# USB_0.net
KiCad netlist of a schematic drawn in Altium Designer
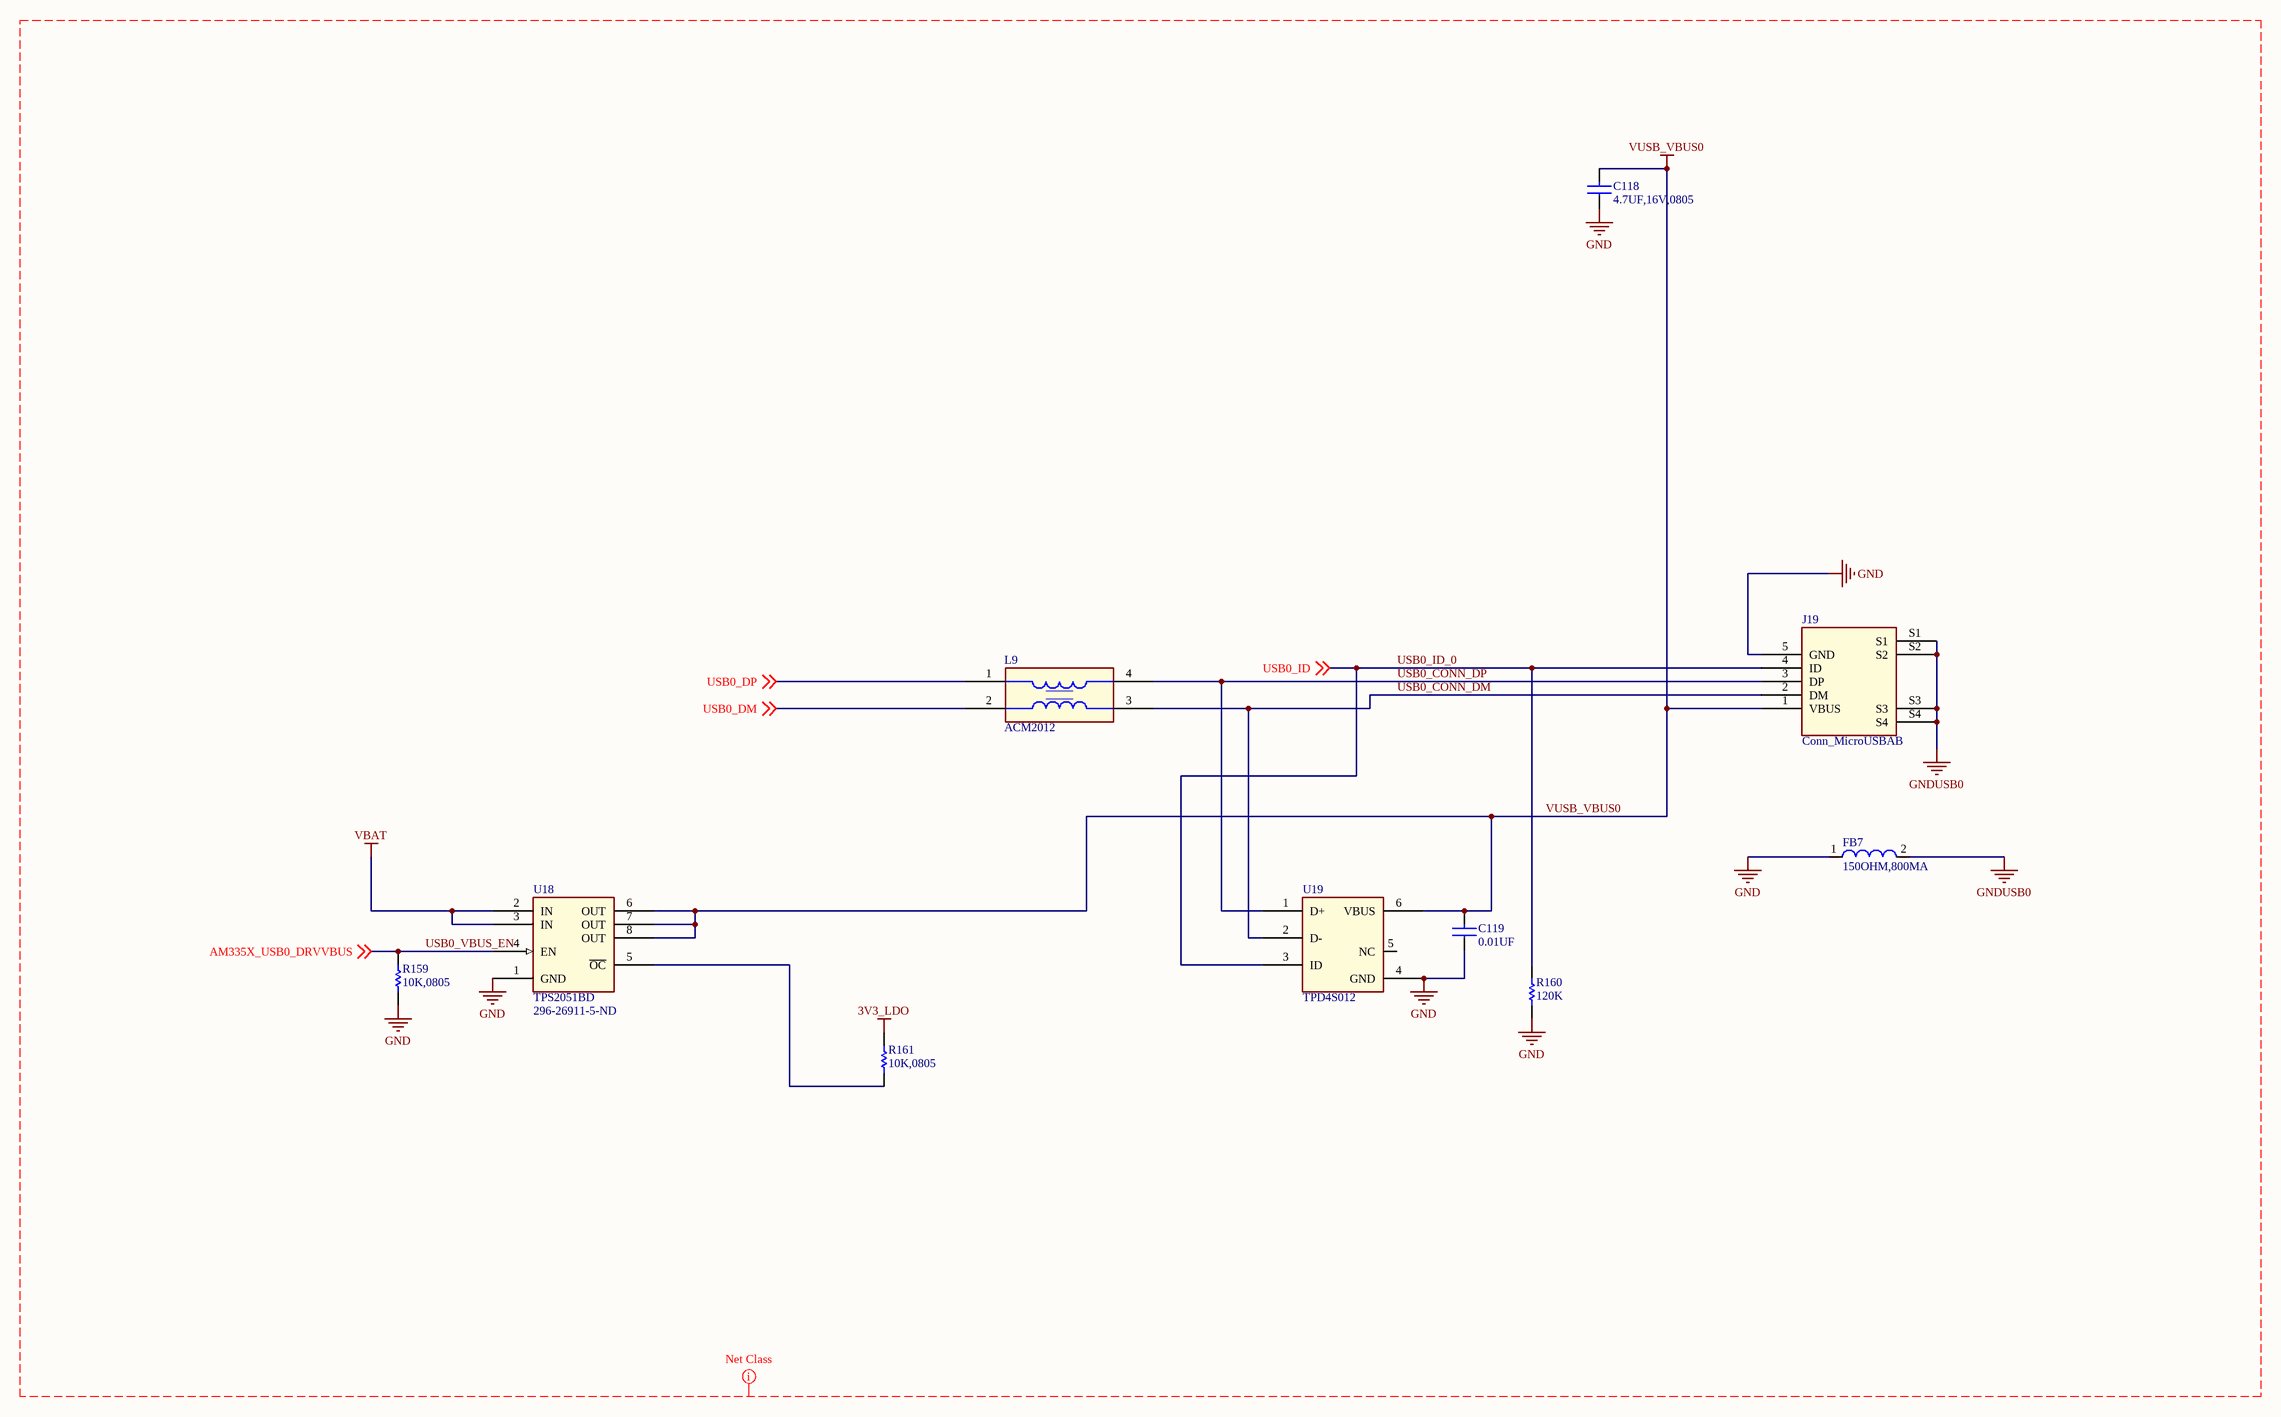
[diagram p0: USB_0.SchDoc]

(export (version "E")
  (design (tool "Eeschema 10.0.6"))
  (components
    (comp (ref "C118")
      (value "4.7UF,16V,0805")
      (footprint "0805")
      (description "AVX - 0805YC475KAT2A - CAP, MLCC, X7R, 4.7UF, 16V, 0805")
      (fields (field (name "MANUFACTURER") "AVX") (field (name "MANUFACTURER PART NUMBER") "0805YC475KAT2A"))
      (libsource (lib "LINUX") (part "4.7UF,16V,0805"))
    )
    (comp (ref "C119")
      (value "0.01UF")
      (footprint "0805")
      (description "MULTICOMP - MCSH21B103K100CT - CAP, MLCC, X7R, 10NF, 10V, 0805")
      (fields
        (field (name "MANUFACTURER") "MULTICOMP")
        (field (name "MANUFACTURER PART NUMBER") "MCSH21B103K100CT")
      )
      (libsource (lib "LINUX") (part "0.01UF"))
    )
    (comp (ref "FB7")
      (value "150OHM,800MA")
      (footprint "0805")
      (description "FERRITE 800MA 150 OHM 0805 SMD")
      (fields
        (field (name "MANUFACTURER") "Laird-Signal Integrity Products")
        (field (name "MANUFACTURER PART NUMBER") "LI0805H151R-10")
      )
      (libsource (lib "LINUX") (part "150OHM,800MA"))
    )
    (comp (ref "J19")
      (value "Conn_MicroUSBAB")
      (footprint "USB MINI TYPE B")
      (description "Connector Micro USB AB RA")
      (fields (field (name "TIINTPARTNUMBER") "2C0088") (field (name "MFR") "Hirose"))
      (libsource (lib "LINUX") (part "Conn_MicroUSBAB"))
    )
    (comp (ref "L9")
      (value "ACM2012")
      (footprint "ACM2012H")
      (description "Common Mode Filter for USB/HDMI")
      (fields (field (name "MFR") "TDK") (field (name "TIINTPARTNUMBER") "1M0003"))
      (libsource (lib "LINUX") (part "ACM2012"))
    )
    (comp (ref "R159")
      (value "10K,0805")
      (footprint "0805")
      (description "BOURNS - CR0805-FX-1002GLF - RESISTOR, 10K, 0.125W, 1%")
      (fields
        (field (name "MANUFACTURER") "BOURNS")
        (field (name "MANUFACTURER PART NUMBER") "CR0805-FX-1002GLF")
      )
      (libsource (lib "LINUX") (part "10K,0805"))
    )
    (comp (ref "R160")
      (value "120K")
      (footprint "0805")
      (description "TE CONNECTIVITY - CRGH0805F120K - RESISTOR, POWER, 120K, 0.33W, 1%, 0805")
      (fields
        (field (name "MANUFACTURER") "TE CONNECTIVITY")
        (field (name "MANUFACTURER PART NUMBER") "CRGH0805F120K")
      )
      (libsource (lib "LINUX") (part "120K"))
    )
    (comp (ref "R161")
      (value "10K,0805")
      (footprint "0805")
      (description "BOURNS - CR0805-FX-1002GLF - RESISTOR, 10K, 0.125W, 1%")
      (fields
        (field (name "MANUFACTURER") "BOURNS")
        (field (name "MANUFACTURER PART NUMBER") "CR0805-FX-1002GLF")
      )
      (libsource (lib "LINUX") (part "10K,0805"))
    )
    (comp (ref "U18")
      (value "TPS2051BD")
      (footprint "U_8_D")
      (description "Power Distribution Switch Current Limited 500mA")
      (fields
        (field (name "MFR") "TI")
        (field (name "TIINTPARTNUMBER") "1A0286")
        (field (name "SUPPLIER PART NUMBER 1") "296-26911-5-ND")
      )
      (libsource (lib "LINUX") (part "TPS2051BD"))
    )
    (comp (ref "U19")
      (value "TPD4S012")
      (footprint "U_6_DRY")
      (description "ESD 4channel USB Interface")
      (fields (field (name "MFR") "TI") (field (name "TIINTPARTNUMBER") "1A0233"))
      (libsource (lib "LINUX") (part "TPD4S012"))
    )
  )
  (nets
    (net (code "1") (name "/USB0_CONN_DM") (class "Default")
      (node (ref "J19") (pin "2") (pinfunction "DM_2") (pintype "passive"))
      (node (ref "L9") (pin "3") (pinfunction "3_3") (pintype "passive"))
      (node (ref "U19") (pin "2") (pinfunction "D-_2") (pintype "passive"))
    )
    (net (code "2") (name "/USB0_CONN_DP") (class "Default")
      (node (ref "J19") (pin "3") (pinfunction "DP_3") (pintype "passive"))
      (node (ref "L9") (pin "4") (pinfunction "4_4") (pintype "passive"))
      (node (ref "U19") (pin "1") (pinfunction "D+_1") (pintype "passive"))
    )
    (net (code "3") (name "3V3_LDO") (class "Default")
      (node (ref "R161") (pin "2") (pinfunction "2_2") (pintype "passive"))
    )
    (net (code "4") (name "AM335X_USB0_DRVVBUS") (class "Default")
      (node (ref "R159") (pin "2") (pinfunction "2_2") (pintype "passive"))
      (node (ref "U18") (pin "4") (pinfunction "EN_4") (pintype "input"))
    )
    (net (code "5") (name "GND") (class "Default")
      (node (ref "C118") (pin "1") (pinfunction "1_1") (pintype "passive"))
      (node (ref "C119") (pin "1") (pinfunction "1_1") (pintype "passive"))
      (node (ref "FB7") (pin "1") (pinfunction "1_1") (pintype "passive"))
      (node (ref "J19") (pin "5") (pinfunction "GND_5") (pintype "passive"))
      (node (ref "R159") (pin "1") (pinfunction "1_1") (pintype "passive"))
      (node (ref "R160") (pin "1") (pinfunction "1_1") (pintype "passive"))
      (node (ref "U18") (pin "1") (pinfunction "GND_1") (pintype "power_in"))
      (node (ref "U19") (pin "4") (pinfunction "GND_4") (pintype "power_in"))
    )
    (net (code "6") (name "GNDUSB0") (class "Default")
      (node (ref "FB7") (pin "2") (pinfunction "2_2") (pintype "passive"))
      (node (ref "J19") (pin "S1") (pinfunction "S1_S1") (pintype "power_in"))
      (node (ref "J19") (pin "S2") (pinfunction "S2_S2") (pintype "power_in"))
      (node (ref "J19") (pin "S3") (pinfunction "S3_S3") (pintype "power_in"))
      (node (ref "J19") (pin "S4") (pinfunction "S4_S4") (pintype "power_in"))
    )
    (net (code "7") (name "Net-(U18-~{OC})") (class "Default")
      (node (ref "R161") (pin "1") (pinfunction "1_1") (pintype "passive"))
      (node (ref "U18") (pin "5") (pinfunction "~{OC}_5") (pintype "open_collector"))
    )
    (net (code "8") (name "USB0_DM") (class "Default")
      (node (ref "L9") (pin "2") (pinfunction "2_2") (pintype "passive"))
    )
    (net (code "9") (name "USB0_DP") (class "Default")
      (node (ref "L9") (pin "1") (pinfunction "1_1") (pintype "passive"))
    )
    (net (code "10") (name "USB0_ID") (class "Default")
      (node (ref "J19") (pin "4") (pinfunction "ID_4") (pintype "passive"))
      (node (ref "R160") (pin "2") (pinfunction "2_2") (pintype "passive"))
      (node (ref "U19") (pin "3") (pinfunction "ID_3") (pintype "passive"))
    )
    (net (code "11") (name "VBAT") (class "Default")
      (node (ref "U18") (pin "2") (pinfunction "IN_2") (pintype "power_in"))
      (node (ref "U18") (pin "3") (pinfunction "IN_3") (pintype "power_in"))
    )
    (net (code "12") (name "VUSB_VBUS0") (class "Default")
      (node (ref "C118") (pin "2") (pinfunction "2_2") (pintype "passive"))
      (node (ref "C119") (pin "2") (pinfunction "2_2") (pintype "passive"))
      (node (ref "J19") (pin "1") (pinfunction "VBUS_1") (pintype "passive"))
      (node (ref "U18") (pin "6") (pinfunction "OUT_6") (pintype "power_in"))
      (node (ref "U18") (pin "7") (pinfunction "OUT_7") (pintype "power_in"))
      (node (ref "U18") (pin "8") (pinfunction "OUT_8") (pintype "power_in"))
      (node (ref "U19") (pin "6") (pinfunction "VBUS_6") (pintype "power_in"))
    )
    (net (code "13") (name "unconnected-(U19-NC-Pad5)") (class "Default")
      (node (ref "U19") (pin "5") (pinfunction "NC_5") (pintype "passive"))
    )
  )
)
